# MCU.net
KiCad netlist of a schematic drawn in Altium Designer
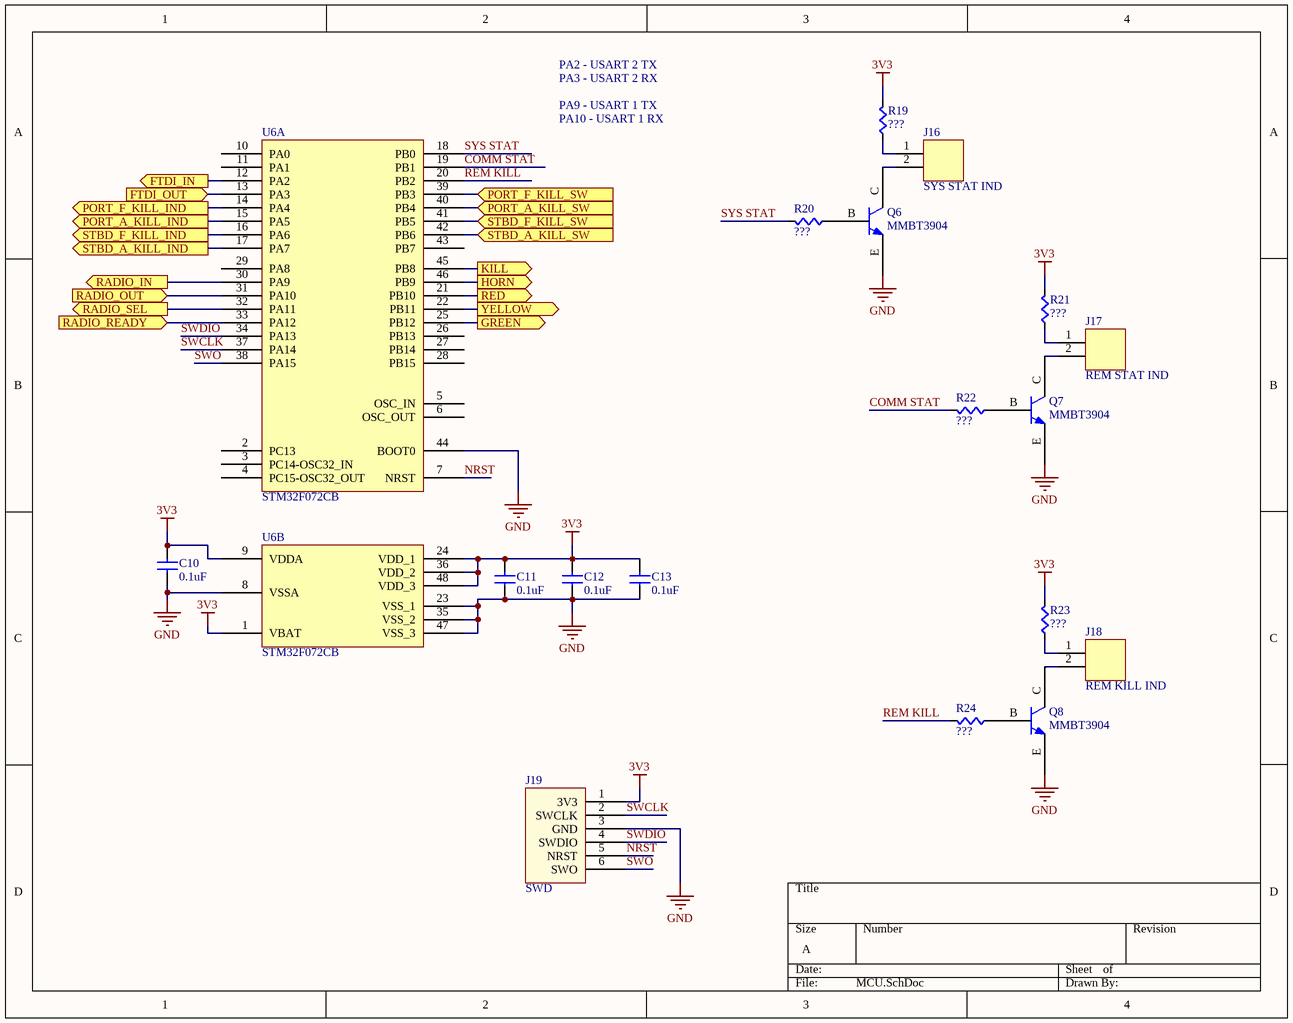
[diagram p0: MCU.SchDoc]

(export (version "E")
  (design (tool "Eeschema 10.0.6"))
  (components
    (comp (ref "C10")
      (value "0.1uF")
      (footprint "CAPC0603")
      (fields (field (name "Comment") "Cap"))
      (libsource (lib "Passives") (part "Cap"))
    )
    (comp (ref "C11")
      (value "0.1uF")
      (footprint "CAPC0603")
      (fields (field (name "Comment") "Cap"))
      (libsource (lib "Passives") (part "Cap"))
    )
    (comp (ref "C12")
      (value "0.1uF")
      (footprint "CAPC0603")
      (fields (field (name "Comment") "Cap"))
      (libsource (lib "Passives") (part "Cap"))
    )
    (comp (ref "C13")
      (value "0.1uF")
      (footprint "CAPC0603")
      (fields (field (name "Comment") "Cap"))
      (libsource (lib "Passives") (part "Cap"))
    )
    (comp (ref "J16")
      (value "SYS STAT IND")
      (footprint "MOLEX-HDR-1X2-SHERLOCK-VERT")
      (libsource (lib "Connectors") (part "MOLEX-HDR-1x2-SHERLOCK_VERT"))
    )
    (comp (ref "J17")
      (value "REM STAT IND")
      (footprint "MOLEX-HDR-1X2-SHERLOCK-VERT")
      (libsource (lib "Connectors") (part "MOLEX-HDR-1x2-SHERLOCK_VERT"))
    )
    (comp (ref "J18")
      (value "REM KILL IND")
      (footprint "MOLEX-HDR-1X2-SHERLOCK-VERT")
      (libsource (lib "Connectors") (part "MOLEX-HDR-1x2-SHERLOCK_VERT"))
    )
    (comp (ref "J19")
      (value "SWD")
      (footprint "SWD_STM32")
      (description "SWD connector matching the pinout on STM Discovery Boards")
      (libsource (lib "Connectors") (part "SWD_STM32"))
    )
    (comp (ref "Q6")
      (value "MMBT3904")
      (footprint "MMBT3904")
      (description "TRANS NPN 40V 0.2A SOT-23")
      (libsource (lib "Semiconductors") (part "MMBT3904"))
    )
    (comp (ref "Q7")
      (value "MMBT3904")
      (footprint "MMBT3904")
      (description "TRANS NPN 40V 0.2A SOT-23")
      (libsource (lib "Semiconductors") (part "MMBT3904"))
    )
    (comp (ref "Q8")
      (value "MMBT3904")
      (footprint "MMBT3904")
      (description "TRANS NPN 40V 0.2A SOT-23")
      (libsource (lib "Semiconductors") (part "MMBT3904"))
    )
    (comp (ref "R19")
      (value "???")
      (footprint "RES0603")
      (fields (field (name "Comment") "Res"))
      (libsource (lib "Passives") (part "Res"))
    )
    (comp (ref "R20")
      (value "???")
      (footprint "RES0603")
      (fields (field (name "Comment") "Res"))
      (libsource (lib "Passives") (part "Res"))
    )
    (comp (ref "R21")
      (value "???")
      (footprint "RES0603")
      (fields (field (name "Comment") "Res"))
      (libsource (lib "Passives") (part "Res"))
    )
    (comp (ref "R22")
      (value "???")
      (footprint "RES0603")
      (fields (field (name "Comment") "Res"))
      (libsource (lib "Passives") (part "Res"))
    )
    (comp (ref "R23")
      (value "???")
      (footprint "RES0603")
      (fields (field (name "Comment") "Res"))
      (libsource (lib "Passives") (part "Res"))
    )
    (comp (ref "R24")
      (value "???")
      (footprint "RES0603")
      (fields (field (name "Comment") "Res"))
      (libsource (lib "Passives") (part "Res"))
    )
    (comp (ref "U6")
      (value "STM32F072CB")
      (footprint "STM32F072CB")
      (description "MCU 32BIT 128KB FLASH 48LQFP")
      (libsource (lib "ICs") (part "STM32F072CB"))
    )
  )
  (nets
    (net (code "1") (name "/COMM STAT") (class "Default")
      (node (ref "R22") (pin "1") (pinfunction "A_1") (pintype "passive"))
      (node (ref "U6") (pin "19") (pinfunction "PB1_19") (pintype "passive"))
    )
    (net (code "2") (name "/FTDI_IN") (class "Default")
      (node (ref "U6") (pin "12") (pinfunction "PA2_12") (pintype "passive"))
    )
    (net (code "3") (name "/FTDI_OUT") (class "Default")
      (node (ref "U6") (pin "13") (pinfunction "PA3_13") (pintype "passive"))
    )
    (net (code "4") (name "/GREEN") (class "Default")
      (node (ref "U6") (pin "25") (pinfunction "PB12_25") (pintype "passive"))
    )
    (net (code "5") (name "/HORN") (class "Default")
      (node (ref "U6") (pin "46") (pinfunction "PB9_46") (pintype "passive"))
    )
    (net (code "6") (name "/KILL") (class "Default")
      (node (ref "U6") (pin "45") (pinfunction "PB8_45") (pintype "passive"))
    )
    (net (code "7") (name "/NRST") (class "Default")
      (node (ref "J19") (pin "5") (pinfunction "NRST_5") (pintype "passive"))
      (node (ref "U6") (pin "7") (pinfunction "NRST_7") (pintype "passive"))
    )
    (net (code "8") (name "/PORT_A_KILL_IND") (class "Default")
      (node (ref "U6") (pin "15") (pinfunction "PA5_15") (pintype "passive"))
    )
    (net (code "9") (name "/PORT_A_KILL_SW") (class "Default")
      (node (ref "U6") (pin "40") (pinfunction "PB4_40") (pintype "passive"))
    )
    (net (code "10") (name "/PORT_F_KILL_IND") (class "Default")
      (node (ref "U6") (pin "14") (pinfunction "PA4_14") (pintype "passive"))
    )
    (net (code "11") (name "/PORT_F_KILL_SW") (class "Default")
      (node (ref "U6") (pin "39") (pinfunction "PB3_39") (pintype "passive"))
    )
    (net (code "12") (name "/RADIO_IN") (class "Default")
      (node (ref "U6") (pin "30") (pinfunction "PA9_30") (pintype "passive"))
    )
    (net (code "13") (name "/RADIO_OUT") (class "Default")
      (node (ref "U6") (pin "31") (pinfunction "PA10_31") (pintype "passive"))
    )
    (net (code "14") (name "/RADIO_READY") (class "Default")
      (node (ref "U6") (pin "33") (pinfunction "PA12_33") (pintype "passive"))
    )
    (net (code "15") (name "/RADIO_SEL") (class "Default")
      (node (ref "U6") (pin "32") (pinfunction "PA11_32") (pintype "passive"))
    )
    (net (code "16") (name "/RED") (class "Default")
      (node (ref "U6") (pin "21") (pinfunction "PB10_21") (pintype "passive"))
    )
    (net (code "17") (name "/REM KILL") (class "Default")
      (node (ref "R24") (pin "1") (pinfunction "A_1") (pintype "passive"))
      (node (ref "U6") (pin "20") (pinfunction "PB2_20") (pintype "passive"))
    )
    (net (code "18") (name "/STBD_A_KILL_IND") (class "Default")
      (node (ref "U6") (pin "17") (pinfunction "PA7_17") (pintype "passive"))
    )
    (net (code "19") (name "/STBD_A_KILL_SW") (class "Default")
      (node (ref "U6") (pin "42") (pinfunction "PB6_42") (pintype "passive"))
    )
    (net (code "20") (name "/STBD_F_KILL_IND") (class "Default")
      (node (ref "U6") (pin "16") (pinfunction "PA6_16") (pintype "passive"))
    )
    (net (code "21") (name "/STBD_F_KILL_SW") (class "Default")
      (node (ref "U6") (pin "41") (pinfunction "PB5_41") (pintype "passive"))
    )
    (net (code "22") (name "/SWCLK") (class "Default")
      (node (ref "J19") (pin "2") (pinfunction "SWCLK_2") (pintype "passive"))
      (node (ref "U6") (pin "37") (pinfunction "PA14_37") (pintype "passive"))
    )
    (net (code "23") (name "/SWDIO") (class "Default")
      (node (ref "J19") (pin "4") (pinfunction "SWDIO_4") (pintype "passive"))
      (node (ref "U6") (pin "34") (pinfunction "PA13_34") (pintype "passive"))
    )
    (net (code "24") (name "/SWO") (class "Default")
      (node (ref "J19") (pin "6") (pinfunction "SWO_6") (pintype "passive"))
      (node (ref "U6") (pin "38") (pinfunction "PA15_38") (pintype "passive"))
    )
    (net (code "25") (name "/SYS STAT") (class "Default")
      (node (ref "R20") (pin "1") (pinfunction "A_1") (pintype "passive"))
      (node (ref "U6") (pin "18") (pinfunction "PB0_18") (pintype "passive"))
    )
    (net (code "26") (name "/YELLOW") (class "Default")
      (node (ref "U6") (pin "22") (pinfunction "PB11_22") (pintype "passive"))
    )
    (net (code "27") (name "3V3") (class "Default")
      (node (ref "C10") (pin "1") (pinfunction "A_1") (pintype "passive"))
      (node (ref "C11") (pin "1") (pinfunction "A_1") (pintype "passive"))
      (node (ref "C12") (pin "1") (pinfunction "A_1") (pintype "passive"))
      (node (ref "C13") (pin "1") (pinfunction "A_1") (pintype "passive"))
      (node (ref "J19") (pin "1") (pinfunction "3V3_1") (pintype "passive"))
      (node (ref "R19") (pin "1") (pinfunction "A_1") (pintype "passive"))
      (node (ref "R21") (pin "1") (pinfunction "A_1") (pintype "passive"))
      (node (ref "R23") (pin "1") (pinfunction "A_1") (pintype "passive"))
      (node (ref "U6") (pin "1") (pinfunction "VBAT_1") (pintype "passive"))
      (node (ref "U6") (pin "24") (pinfunction "VDD_1_24") (pintype "passive"))
      (node (ref "U6") (pin "36") (pinfunction "VDD_2_36") (pintype "passive"))
      (node (ref "U6") (pin "48") (pinfunction "VDD_3_48") (pintype "passive"))
      (node (ref "U6") (pin "9") (pinfunction "VDDA_9") (pintype "passive"))
    )
    (net (code "28") (name "GND") (class "Default")
      (node (ref "C10") (pin "2") (pinfunction "B_2") (pintype "passive"))
      (node (ref "C11") (pin "2") (pinfunction "B_2") (pintype "passive"))
      (node (ref "C12") (pin "2") (pinfunction "B_2") (pintype "passive"))
      (node (ref "C13") (pin "2") (pinfunction "B_2") (pintype "passive"))
      (node (ref "J19") (pin "3") (pinfunction "GND_3") (pintype "passive"))
      (node (ref "Q6") (pin "E") (pinfunction "E_E") (pintype "passive"))
      (node (ref "Q7") (pin "E") (pinfunction "E_E") (pintype "passive"))
      (node (ref "Q8") (pin "E") (pinfunction "E_E") (pintype "passive"))
      (node (ref "U6") (pin "23") (pinfunction "VSS_1_23") (pintype "passive"))
      (node (ref "U6") (pin "35") (pinfunction "VSS_2_35") (pintype "passive"))
      (node (ref "U6") (pin "44") (pinfunction "BOOT0_44") (pintype "passive"))
      (node (ref "U6") (pin "47") (pinfunction "VSS_3_47") (pintype "passive"))
      (node (ref "U6") (pin "8") (pinfunction "VSSA_8") (pintype "passive"))
    )
    (net (code "29") (name "Net-(J16-Pad2)") (class "Default")
      (node (ref "J16") (pin "2") (pinfunction "2_2") (pintype "passive"))
      (node (ref "Q6") (pin "C") (pinfunction "C_C") (pintype "passive"))
    )
    (net (code "30") (name "Net-(J17-Pad2)") (class "Default")
      (node (ref "J17") (pin "2") (pinfunction "2_2") (pintype "passive"))
      (node (ref "Q7") (pin "C") (pinfunction "C_C") (pintype "passive"))
    )
    (net (code "31") (name "Net-(J18-Pad2)") (class "Default")
      (node (ref "J18") (pin "2") (pinfunction "2_2") (pintype "passive"))
      (node (ref "Q8") (pin "C") (pinfunction "C_C") (pintype "passive"))
    )
    (net (code "32") (name "Net-(R19-B)") (class "Default")
      (node (ref "J16") (pin "1") (pinfunction "1_1") (pintype "passive"))
      (node (ref "R19") (pin "2") (pinfunction "B_2") (pintype "passive"))
    )
    (net (code "33") (name "Net-(R20-B)") (class "Default")
      (node (ref "Q6") (pin "B") (pinfunction "B_B") (pintype "passive"))
      (node (ref "R20") (pin "2") (pinfunction "B_2") (pintype "passive"))
    )
    (net (code "34") (name "Net-(R21-B)") (class "Default")
      (node (ref "J17") (pin "1") (pinfunction "1_1") (pintype "passive"))
      (node (ref "R21") (pin "2") (pinfunction "B_2") (pintype "passive"))
    )
    (net (code "35") (name "Net-(R22-B)") (class "Default")
      (node (ref "Q7") (pin "B") (pinfunction "B_B") (pintype "passive"))
      (node (ref "R22") (pin "2") (pinfunction "B_2") (pintype "passive"))
    )
    (net (code "36") (name "Net-(R23-B)") (class "Default")
      (node (ref "J18") (pin "1") (pinfunction "1_1") (pintype "passive"))
      (node (ref "R23") (pin "2") (pinfunction "B_2") (pintype "passive"))
    )
    (net (code "37") (name "Net-(R24-B)") (class "Default")
      (node (ref "Q8") (pin "B") (pinfunction "B_B") (pintype "passive"))
      (node (ref "R24") (pin "2") (pinfunction "B_2") (pintype "passive"))
    )
    (net (code "38") (name "unconnected-(U6A-OSC_IN-Pad5)") (class "Default")
      (node (ref "U6") (pin "5") (pinfunction "OSC_IN_5") (pintype "passive"))
    )
    (net (code "39") (name "unconnected-(U6A-OSC_OUT-Pad6)") (class "Default")
      (node (ref "U6") (pin "6") (pinfunction "OSC_OUT_6") (pintype "passive"))
    )
    (net (code "40") (name "unconnected-(U6A-PA0-Pad10)") (class "Default")
      (node (ref "U6") (pin "10") (pinfunction "PA0_10") (pintype "passive"))
    )
    (net (code "41") (name "unconnected-(U6A-PA1-Pad11)") (class "Default")
      (node (ref "U6") (pin "11") (pinfunction "PA1_11") (pintype "passive"))
    )
    (net (code "42") (name "unconnected-(U6A-PA8-Pad29)") (class "Default")
      (node (ref "U6") (pin "29") (pinfunction "PA8_29") (pintype "passive"))
    )
    (net (code "43") (name "unconnected-(U6A-PB7-Pad43)") (class "Default")
      (node (ref "U6") (pin "43") (pinfunction "PB7_43") (pintype "passive"))
    )
    (net (code "44") (name "unconnected-(U6A-PB13-Pad26)") (class "Default")
      (node (ref "U6") (pin "26") (pinfunction "PB13_26") (pintype "passive"))
    )
    (net (code "45") (name "unconnected-(U6A-PB14-Pad27)") (class "Default")
      (node (ref "U6") (pin "27") (pinfunction "PB14_27") (pintype "passive"))
    )
    (net (code "46") (name "unconnected-(U6A-PB15-Pad28)") (class "Default")
      (node (ref "U6") (pin "28") (pinfunction "PB15_28") (pintype "passive"))
    )
    (net (code "47") (name "unconnected-(U6A-PC13-Pad2)") (class "Default")
      (node (ref "U6") (pin "2") (pinfunction "PC13_2") (pintype "passive"))
    )
    (net (code "48") (name "unconnected-(U6A-PC14-OSC32_IN-Pad3)") (class "Default")
      (node (ref "U6") (pin "3") (pinfunction "PC14-OSC32_IN_3") (pintype "passive"))
    )
    (net (code "49") (name "unconnected-(U6A-PC15-OSC32_OUT-Pad4)") (class "Default")
      (node (ref "U6") (pin "4") (pinfunction "PC15-OSC32_OUT_4") (pintype "passive"))
    )
  )
)
